# TS8.net
KiCad netlist of a schematic drawn in EAGLE
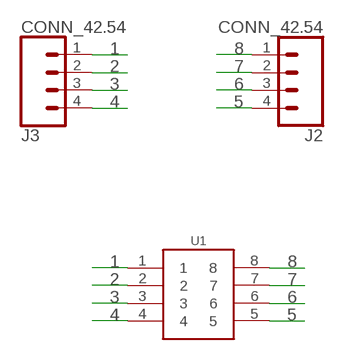
[diagram p0: schematic, sheet 1]

(export (version "E")
  (design (tool "Eeschema 10.0.6"))
  (components
    (comp (ref "J2")
      (value "CONN_42.54")
      (footprint "eagle-import:1X04")
      (libsource (lib "eagle-import") (part "CONN_42.54"))
    )
    (comp (ref "J3")
      (value "CONN_42.54")
      (footprint "eagle-import:1X04")
      (libsource (lib "eagle-import") (part "CONN_42.54"))
    )
    (comp (ref "U1")
      (value "GEN_8TS8")
      (footprint "eagle-import:TS8")
      (libsource (lib "eagle-import") (part "GEN_8TS8"))
    )
  )
  (nets
    (net (code "1") (name "/1") (class "Default")
      (node (ref "J3") (pin "1") (pinfunction "1_1") (pintype "passive"))
      (node (ref "U1") (pin "1") (pinfunction "1_1") (pintype "bidirectional"))
    )
    (net (code "2") (name "/2") (class "Default")
      (node (ref "J3") (pin "2") (pinfunction "2_2") (pintype "passive"))
      (node (ref "U1") (pin "2") (pinfunction "2_2") (pintype "bidirectional"))
    )
    (net (code "3") (name "/3") (class "Default")
      (node (ref "J3") (pin "3") (pinfunction "3_3") (pintype "passive"))
      (node (ref "U1") (pin "3") (pinfunction "3_3") (pintype "bidirectional"))
    )
    (net (code "4") (name "/4") (class "Default")
      (node (ref "J3") (pin "4") (pinfunction "4_4") (pintype "passive"))
      (node (ref "U1") (pin "4") (pinfunction "4_4") (pintype "bidirectional"))
    )
    (net (code "5") (name "/5") (class "Default")
      (node (ref "J2") (pin "4") (pinfunction "4_4") (pintype "passive"))
      (node (ref "U1") (pin "5") (pinfunction "5_5") (pintype "bidirectional"))
    )
    (net (code "6") (name "/6") (class "Default")
      (node (ref "J2") (pin "3") (pinfunction "3_3") (pintype "passive"))
      (node (ref "U1") (pin "6") (pinfunction "6_6") (pintype "bidirectional"))
    )
    (net (code "7") (name "/7") (class "Default")
      (node (ref "J2") (pin "2") (pinfunction "2_2") (pintype "passive"))
      (node (ref "U1") (pin "7") (pinfunction "7_7") (pintype "bidirectional"))
    )
    (net (code "8") (name "/8") (class "Default")
      (node (ref "J2") (pin "1") (pinfunction "1_1") (pintype "passive"))
      (node (ref "U1") (pin "8") (pinfunction "8_8") (pintype "bidirectional"))
    )
  )
)
